# ESP32.net
KiCad netlist of a schematic drawn in Altium Designer
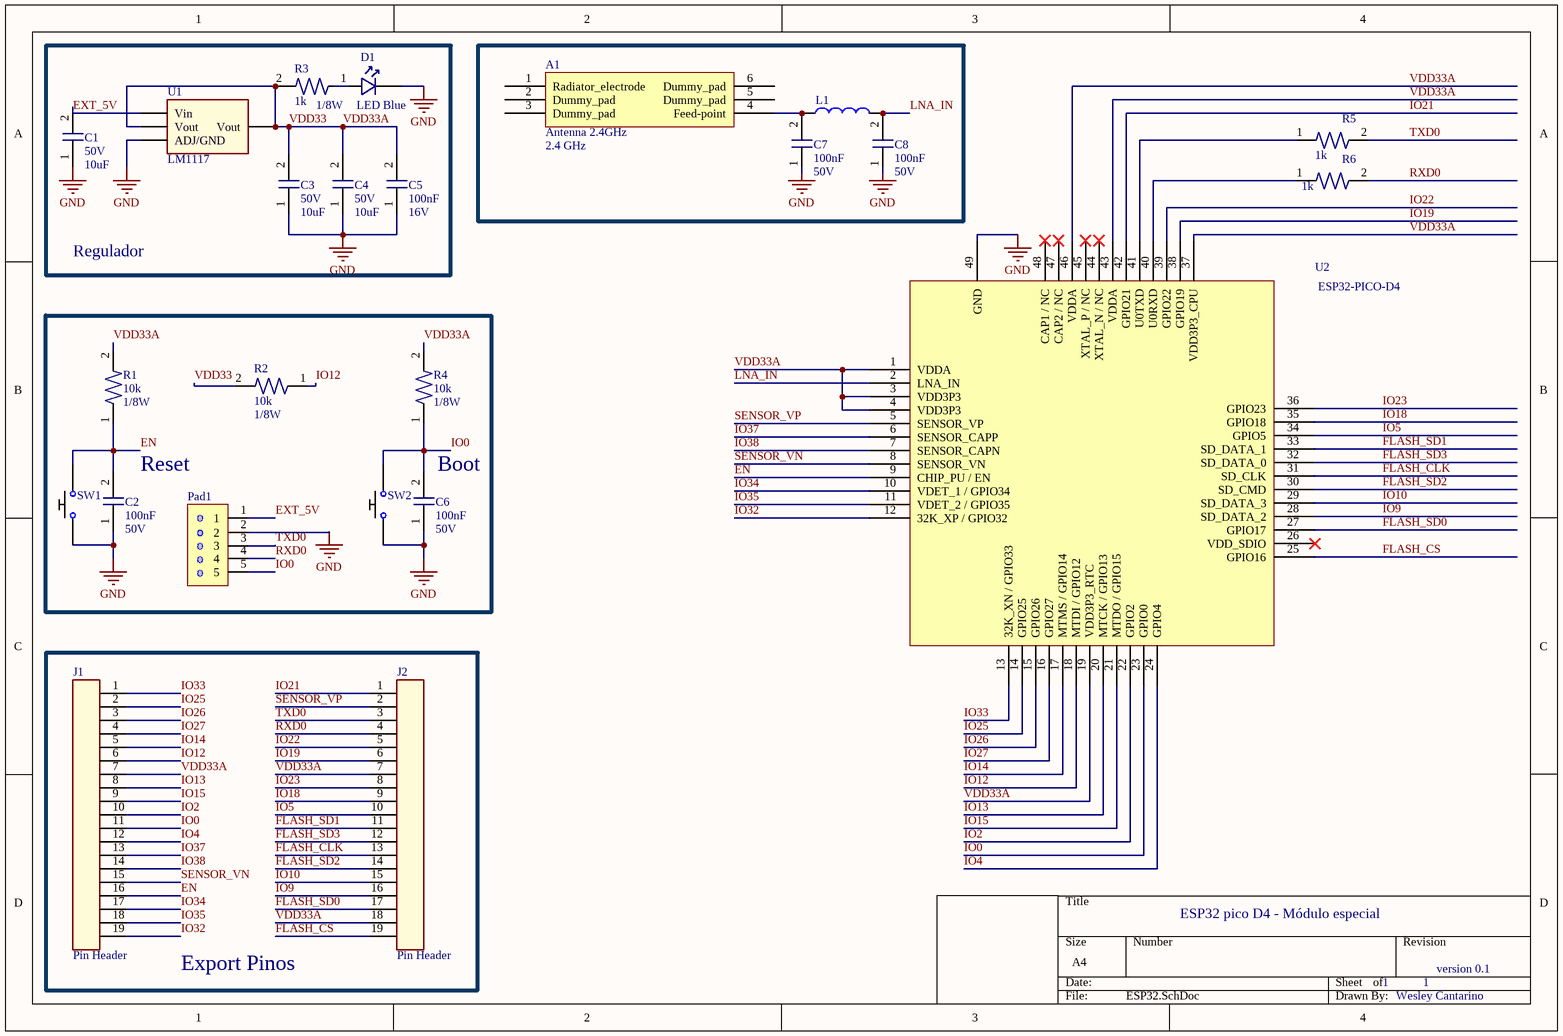
[diagram p0: ESP32.SchDoc]

(export (version "E")
  (design (tool "Eeschema 10.0.6"))
  (components
    (comp (ref "A1")
      (value "Antenna 2.4GHz")
      (footprint "PCBComponent_1")
      (description "SMD Antennas RoHS")
      (fields
        (field (name "MANUFACTURER") "TDK")
        (field (name "MFR.PART #") "ANT016008LCS2442MA2")
        (field (name "FREQUENCY RANGE") "2.4 GHz")
      )
      (libsource (lib "Antenna SMD") (part "Antenna 2.4GHz"))
    )
    (comp (ref "C1")
      (value "CAP 10uF/50V")
      (footprint "CAP 100nF/50V")
      (description "10uF ±1% 50V Ceramic Capacitor C0G, NP0 0805 (2012 Metric)")
      (fields (field (name "VOLTAGE") "50V") (field (name "CAPACITANCE") "10uF"))
      (libsource (lib "Ceramic Capacitors 0805 50V") (part "CAP  10uF/50V"))
    )
    (comp (ref "C2")
      (value "CAP 100nF/50V")
      (footprint "CAP 10uF/6.3V")
      (description "0.1µF ±10% 50V Ceramic Capacitor X5R 0402 (1005 Metric)")
      (fields (field (name "CAPACITANCE") "100nF") (field (name "VOLTAGE") "50V"))
      (libsource (lib "Capacitores SMD ceramicos") (part "CAP 100nF/50V"))
    )
    (comp (ref "C3")
      (value "CAP 10uF/50V")
      (footprint "CAP 22uF/6.3V")
      (description "10uF ±1% 50V Ceramic Capacitor C0G, NP0 0805 (2012 Metric)")
      (fields (field (name "VOLTAGE") "50V") (field (name "CAPACITANCE") "10uF"))
      (libsource (lib "Ceramic Capacitors 0805 50V") (part "CAP  10uF/50V"))
    )
    (comp (ref "C4")
      (value "CAP 10uF/50V")
      (footprint "RES SMD 62k OHM 1% 1/16W 0402")
      (description "10uF ±1% 50V Ceramic Capacitor C0G, NP0 0805 (2012 Metric)")
      (fields (field (name "VOLTAGE") "50V") (field (name "CAPACITANCE") "10uF"))
      (libsource (lib "Ceramic Capacitors 0805 50V") (part "CAP  10uF/50V"))
    )
    (comp (ref "C5")
      (value "CAP 100nF/16V")
      (footprint "RES SMD 200k OHM 1% 1/16W 0402")
      (description "0.1µF ±20% 16V Ceramic Capacitor Y5V (F) 0805 (2012 Metric)")
      (fields (field (name "CAPACITANCE") "100nF") (field (name "VOLTAGE") "16V"))
      (libsource (lib "Ceramic Capacitors 0805 16V") (part "CAP 100nF/16V"))
    )
    (comp (ref "C6")
      (value "CAP 100nF/50V")
      (footprint "CAP 22uF/6.3V")
      (description "0.1µF ±10% 50V Ceramic Capacitor X5R 0402 (1005 Metric)")
      (fields (field (name "CAPACITANCE") "100nF") (field (name "VOLTAGE") "50V"))
      (libsource (lib "Capacitores SMD ceramicos") (part "CAP 100nF/50V"))
    )
    (comp (ref "C7")
      (value "CAP 100nF/50V")
      (footprint "CAP 10uF/6.3V")
      (description "0.1µF ±10% 50V Ceramic Capacitor X5R 0402 (1005 Metric)")
      (fields (field (name "CAPACITANCE") "100nF") (field (name "VOLTAGE") "50V"))
      (libsource (lib "Ceramic Capacitors 0402 50V") (part "CAP 100nF/50V"))
    )
    (comp (ref "C8")
      (value "CAP 100nF/50V")
      (footprint "CAP 10uF/6.3V")
      (description "0.1µF ±10% 50V Ceramic Capacitor X5R 0402 (1005 Metric)")
      (fields (field (name "CAPACITANCE") "100nF") (field (name "VOLTAGE") "50V"))
      (libsource (lib "Ceramic Capacitors 0402 50V") (part "CAP 100nF/50V"))
    )
    (comp (ref "D1")
      (value "LED Blue")
      (footprint "Model Name")
      (description "Blue 470nm LED Indication - Discrete 3.3V 0805 (2012 Metric)")
      (libsource (lib "LEDs") (part "LED Blue"))
    )
    (comp (ref "J1")
      (value "Pin Header")
      (footprint "Pin Header 19 Ways")
      (description "Connector Header PTH 0.100\" (2.54mm)")
      (libsource (lib "") (part "Pin Header 19 ways_1"))
    )
    (comp (ref "J2")
      (value "Pin Header")
      (footprint "Pin Header 19 Ways")
      (description "Connector Header PTH 0.100\" (2.54mm)")
      (libsource (lib "Connectors") (part "Pin Header 19 ways"))
    )
    (comp (ref "L1")
      (value "LBEAD")
      (footprint "CAP 10uF/6.3V")
      (description "Inductor LBEAD")
      (libsource (lib "i9Library_Altium") (part "IND_LBEAD_SMD_1806"))
    )
    (comp (ref "Pad1")
      (value "CN_KK_5")
      (footprint "CN_KK_5_5045-5")
      (description "KK_5")
      (libsource (lib "i9Library_Altium") (part "CN_KK_5"))
    )
    (comp (ref "R1")
      (value "RES 0603")
      (footprint "RES SMD 0 OHM 1/16W 0402")
      (fields (field (name "RESISTENCE") "10k") (field (name "POWER") "1/8W"))
      (libsource (lib "Resistors 0603") (part "RES 10k 1% 1/8W"))
    )
    (comp (ref "R2")
      (value "RES 0603")
      (footprint "RES SMD 0 OHM 1/16W 0402")
      (fields (field (name "RESISTENCE") "10k") (field (name "POWER") "1/8W"))
      (libsource (lib "Resistors 0603") (part "RES 10k 1% 1/8W"))
    )
    (comp (ref "R3")
      (value "RES 0603")
      (footprint "RES SMD 430 OHM 1% 1/16W 0402")
      (fields (field (name "RESISTENCE") "1k") (field (name "POWER") "1/8W"))
      (libsource (lib "Resistors 0603") (part "RES 10k 1% 1/8W"))
    )
    (comp (ref "R4")
      (value "RES 0603")
      (footprint "RES SMD 0 OHM 1/16W 0402")
      (fields (field (name "RESISTENCE") "10k") (field (name "POWER") "1/8W"))
      (libsource (lib "Resistors 0603") (part "RES 10k 1% 1/8W"))
    )
    (comp (ref "R5")
      (value "RES 0603")
      (footprint "RES SMD 0 OHM 1/16W 0402")
      (fields (field (name "RESISTENCE") "1k") (field (name "POWER") "1/8W"))
      (libsource (lib "Resistors 0603") (part "RES 10k 1% 1/8W"))
    )
    (comp (ref "R6")
      (value "RES 0603")
      (footprint "RES SMD 0 OHM 1/16W 0402")
      (fields (field (name "RESISTENCE") "1k") (field (name "POWER") "1/8W"))
      (libsource (lib "Resistors 0603") (part "RES 10k 1% 1/8W"))
    )
    (comp (ref "SW1")
      (value "Tactile Switch SPST 5.10X0.40 mm")
      (footprint "PCBComponent_1")
      (description "TACTILE SWITCHES SPST 5.10MM X 5.10MM 0.40MM 50MA @ 12VDC SMD ROHS")
      (fields (field (name "MANUFACTURER") "XKB Enterprise") (field (name "MFR.PART #") "TS-1187A-B-A-B"))
      (libsource (lib "Tactile Switches SMD") (part "Tactile Switch SPST 5.10X0.40 mm"))
    )
    (comp (ref "SW2")
      (value "Tactile Switch SPST 5.10X0.40 mm")
      (footprint "PCBComponent_1")
      (description "TACTILE SWITCHES SPST 5.10MM X 5.10MM 0.40MM 50MA @ 12VDC SMD ROHS")
      (fields (field (name "MANUFACTURER") "XKB Enterprise") (field (name "MFR.PART #") "TS-1187A-B-A-B"))
      (libsource (lib "Tactile Switches SMD") (part "Tactile Switch SPST 5.10X0.40 mm"))
    )
    (comp (ref "U1")
      (value "LM1117")
      (footprint "LM1117")
      (description "Linear Voltage Regulator IC Positive Fixed 1 Output 3.3V 1A SOT-223")
      (libsource (lib "ICs - Voltage Regulators") (part "LM1117"))
    )
    (comp (ref "U2")
      (value "ESP32-PICO-D4")
      (footprint "*PQFN50P700X700X104-49N")
      (description "RF TRANSCEIVER ICS QFN-48_7X7X05P ROHS")
      (fields (field (name "MANUFACTURER") "Espressif Systems") (field (name "LCSC PART #") "C193707"))
      (libsource (lib "ESP32") (part "ESP32-PICO-D4"))
    )
  )
  (nets
    (net (code "1") (name "/EN") (class "Default")
      (node (ref "C2") (pin "2") (pinfunction "2_2") (pintype "passive"))
      (node (ref "J1") (pin "16") (pinfunction "16_16") (pintype "passive"))
      (node (ref "R1") (pin "1") (pinfunction "1_1") (pintype "passive"))
      (node (ref "SW1") (pin "2") (pinfunction "B_2") (pintype "passive"))
      (node (ref "U2") (pin "9") (pinfunction "CHIP_PU_/_EN_9") (pintype "passive"))
    )
    (net (code "2") (name "/EXT_5V") (class "Default")
      (node (ref "C1") (pin "2") (pinfunction "2_2") (pintype "passive"))
      (node (ref "Pad1") (pin "1") (pinfunction "1_1") (pintype "passive"))
      (node (ref "U1") (pin "3") (pinfunction "Vin_3") (pintype "power_in"))
    )
    (net (code "3") (name "/FLASH_CLK") (class "Default")
      (node (ref "J2") (pin "13") (pinfunction "13_13") (pintype "passive"))
      (node (ref "U2") (pin "31") (pinfunction "SD_CLK_31") (pintype "passive"))
    )
    (net (code "4") (name "/FLASH_CS") (class "Default")
      (node (ref "J2") (pin "19") (pinfunction "19_19") (pintype "passive"))
      (node (ref "U2") (pin "25") (pinfunction "GPIO16_25") (pintype "passive"))
    )
    (net (code "5") (name "/FLASH_SD0") (class "Default")
      (node (ref "J2") (pin "17") (pinfunction "17_17") (pintype "passive"))
      (node (ref "U2") (pin "27") (pinfunction "GPIO17_27") (pintype "passive"))
    )
    (net (code "6") (name "/FLASH_SD1") (class "Default")
      (node (ref "J2") (pin "11") (pinfunction "11_11") (pintype "passive"))
      (node (ref "U2") (pin "33") (pinfunction "SD_DATA_1_33") (pintype "passive"))
    )
    (net (code "7") (name "/FLASH_SD2") (class "Default")
      (node (ref "J2") (pin "14") (pinfunction "14_14") (pintype "passive"))
      (node (ref "U2") (pin "30") (pinfunction "SD_CMD_30") (pintype "passive"))
    )
    (net (code "8") (name "/FLASH_SD3") (class "Default")
      (node (ref "J2") (pin "12") (pinfunction "12_12") (pintype "passive"))
      (node (ref "U2") (pin "32") (pinfunction "SD_DATA_0_32") (pintype "passive"))
    )
    (net (code "9") (name "/IO0") (class "Default")
      (node (ref "C6") (pin "2") (pinfunction "2_2") (pintype "passive"))
      (node (ref "J1") (pin "11") (pinfunction "11_11") (pintype "passive"))
      (node (ref "Pad1") (pin "5") (pinfunction "5_5") (pintype "passive"))
      (node (ref "R4") (pin "1") (pinfunction "1_1") (pintype "passive"))
      (node (ref "SW2") (pin "2") (pinfunction "B_2") (pintype "passive"))
      (node (ref "U2") (pin "23") (pinfunction "GPIO0_23") (pintype "passive"))
    )
    (net (code "10") (name "/IO2") (class "Default")
      (node (ref "J1") (pin "10") (pinfunction "10_10") (pintype "passive"))
      (node (ref "U2") (pin "22") (pinfunction "GPIO2_22") (pintype "passive"))
    )
    (net (code "11") (name "/IO4") (class "Default")
      (node (ref "J1") (pin "12") (pinfunction "12_12") (pintype "passive"))
      (node (ref "U2") (pin "24") (pinfunction "GPIO4_24") (pintype "passive"))
    )
    (net (code "12") (name "/IO5") (class "Default")
      (node (ref "J2") (pin "10") (pinfunction "10_10") (pintype "passive"))
      (node (ref "U2") (pin "34") (pinfunction "GPIO5_34") (pintype "passive"))
    )
    (net (code "13") (name "/IO9") (class "Default")
      (node (ref "J2") (pin "16") (pinfunction "16_16") (pintype "passive"))
      (node (ref "U2") (pin "28") (pinfunction "SD_DATA_2_28") (pintype "passive"))
    )
    (net (code "14") (name "/IO10") (class "Default")
      (node (ref "J2") (pin "15") (pinfunction "15_15") (pintype "passive"))
      (node (ref "U2") (pin "29") (pinfunction "SD_DATA_3_29") (pintype "passive"))
    )
    (net (code "15") (name "/IO12") (class "Default")
      (node (ref "J1") (pin "6") (pinfunction "6_6") (pintype "passive"))
      (node (ref "R2") (pin "1") (pinfunction "1_1") (pintype "passive"))
      (node (ref "U2") (pin "18") (pinfunction "MTDI_/_GPIO12_18") (pintype "passive"))
    )
    (net (code "16") (name "/IO13") (class "Default")
      (node (ref "J1") (pin "8") (pinfunction "8_8") (pintype "passive"))
      (node (ref "U2") (pin "20") (pinfunction "MTCK_/_GPIO13_20") (pintype "passive"))
    )
    (net (code "17") (name "/IO14") (class "Default")
      (node (ref "J1") (pin "5") (pinfunction "5_5") (pintype "passive"))
      (node (ref "U2") (pin "17") (pinfunction "MTMS_/_GPIO14_17") (pintype "passive"))
    )
    (net (code "18") (name "/IO15") (class "Default")
      (node (ref "J1") (pin "9") (pinfunction "9_9") (pintype "passive"))
      (node (ref "U2") (pin "21") (pinfunction "MTDO_/_GPIO15_21") (pintype "passive"))
    )
    (net (code "19") (name "/IO18") (class "Default")
      (node (ref "J2") (pin "9") (pinfunction "9_9") (pintype "passive"))
      (node (ref "U2") (pin "35") (pinfunction "GPIO18_35") (pintype "passive"))
    )
    (net (code "20") (name "/IO19") (class "Default")
      (node (ref "J2") (pin "6") (pinfunction "6_6") (pintype "passive"))
      (node (ref "U2") (pin "38") (pinfunction "GPIO19_38") (pintype "passive"))
    )
    (net (code "21") (name "/IO21") (class "Default")
      (node (ref "J2") (pin "1") (pinfunction "1_1") (pintype "passive"))
      (node (ref "U2") (pin "42") (pinfunction "GPIO21_42") (pintype "passive"))
    )
    (net (code "22") (name "/IO22") (class "Default")
      (node (ref "J2") (pin "5") (pinfunction "5_5") (pintype "passive"))
      (node (ref "U2") (pin "39") (pinfunction "GPIO22_39") (pintype "passive"))
    )
    (net (code "23") (name "/IO23") (class "Default")
      (node (ref "J2") (pin "8") (pinfunction "8_8") (pintype "passive"))
      (node (ref "U2") (pin "36") (pinfunction "GPIO23_36") (pintype "passive"))
    )
    (net (code "24") (name "/IO25") (class "Default")
      (node (ref "J1") (pin "2") (pinfunction "2_2") (pintype "passive"))
      (node (ref "U2") (pin "14") (pinfunction "GPIO25_14") (pintype "passive"))
    )
    (net (code "25") (name "/IO26") (class "Default")
      (node (ref "J1") (pin "3") (pinfunction "3_3") (pintype "passive"))
      (node (ref "U2") (pin "15") (pinfunction "GPIO26_15") (pintype "passive"))
    )
    (net (code "26") (name "/IO27") (class "Default")
      (node (ref "J1") (pin "4") (pinfunction "4_4") (pintype "passive"))
      (node (ref "U2") (pin "16") (pinfunction "GPIO27_16") (pintype "passive"))
    )
    (net (code "27") (name "/IO32") (class "Default")
      (node (ref "J1") (pin "19") (pinfunction "19_19") (pintype "passive"))
      (node (ref "U2") (pin "12") (pinfunction "32K_XP_/_GPIO32_12") (pintype "passive"))
    )
    (net (code "28") (name "/IO33") (class "Default")
      (node (ref "J1") (pin "1") (pinfunction "1_1") (pintype "passive"))
      (node (ref "U2") (pin "13") (pinfunction "32K_XN_/_GPIO33_13") (pintype "passive"))
    )
    (net (code "29") (name "/IO34") (class "Default")
      (node (ref "J1") (pin "17") (pinfunction "17_17") (pintype "passive"))
      (node (ref "U2") (pin "10") (pinfunction "VDET_1_/_GPIO34_10") (pintype "passive"))
    )
    (net (code "30") (name "/IO35") (class "Default")
      (node (ref "J1") (pin "18") (pinfunction "18_18") (pintype "passive"))
      (node (ref "U2") (pin "11") (pinfunction "VDET_2_/_GPIO35_11") (pintype "passive"))
    )
    (net (code "31") (name "/IO37") (class "Default")
      (node (ref "J1") (pin "13") (pinfunction "13_13") (pintype "passive"))
      (node (ref "U2") (pin "6") (pinfunction "SENSOR_CAPP_6") (pintype "passive"))
    )
    (net (code "32") (name "/IO38") (class "Default")
      (node (ref "J1") (pin "14") (pinfunction "14_14") (pintype "passive"))
      (node (ref "U2") (pin "7") (pinfunction "SENSOR_CAPN_7") (pintype "passive"))
    )
    (net (code "33") (name "/LNA_IN") (class "Default")
      (node (ref "C8") (pin "2") (pinfunction "2_2") (pintype "passive"))
      (node (ref "L1") (pin "2") (pintype "passive"))
      (node (ref "U2") (pin "2") (pinfunction "LNA_IN_2") (pintype "passive"))
    )
    (net (code "34") (name "/RXD0") (class "Default")
      (node (ref "J2") (pin "4") (pinfunction "4_4") (pintype "passive"))
      (node (ref "Pad1") (pin "4") (pinfunction "4_4") (pintype "passive"))
      (node (ref "R6") (pin "2") (pinfunction "2_2") (pintype "passive"))
    )
    (net (code "35") (name "/SENSOR_VN") (class "Default")
      (node (ref "J1") (pin "15") (pinfunction "15_15") (pintype "passive"))
      (node (ref "U2") (pin "8") (pinfunction "SENSOR_VN_8") (pintype "passive"))
    )
    (net (code "36") (name "/SENSOR_VP") (class "Default")
      (node (ref "J2") (pin "2") (pinfunction "2_2") (pintype "passive"))
      (node (ref "U2") (pin "5") (pinfunction "SENSOR_VP_5") (pintype "passive"))
    )
    (net (code "37") (name "/TXD0") (class "Default")
      (node (ref "J2") (pin "3") (pinfunction "3_3") (pintype "passive"))
      (node (ref "Pad1") (pin "3") (pinfunction "3_3") (pintype "passive"))
      (node (ref "R5") (pin "2") (pinfunction "2_2") (pintype "passive"))
    )
    (net (code "38") (name "/VDD33") (class "Default")
      (node (ref "C3") (pin "2") (pinfunction "2_2") (pintype "passive"))
      (node (ref "C4") (pin "2") (pinfunction "2_2") (pintype "passive"))
      (node (ref "C5") (pin "2") (pinfunction "2_2") (pintype "passive"))
      (node (ref "J1") (pin "7") (pinfunction "7_7") (pintype "passive"))
      (node (ref "J2") (pin "18") (pinfunction "18_18") (pintype "passive"))
      (node (ref "J2") (pin "7") (pinfunction "7_7") (pintype "passive"))
      (node (ref "R1") (pin "2") (pinfunction "2_2") (pintype "passive"))
      (node (ref "R2") (pin "2") (pinfunction "2_2") (pintype "passive"))
      (node (ref "R3") (pin "2") (pinfunction "2_2") (pintype "passive"))
      (node (ref "R4") (pin "2") (pinfunction "2_2") (pintype "passive"))
      (node (ref "U1") (pin "2") (pinfunction "Vout_2") (pintype "power_in"))
      (node (ref "U1") (pin "4") (pinfunction "Vout_4") (pintype "power_in"))
      (node (ref "U2") (pin "1") (pinfunction "VDDA_1") (pintype "passive"))
      (node (ref "U2") (pin "19") (pinfunction "VDD3P3_RTC_19") (pintype "passive"))
      (node (ref "U2") (pin "3") (pinfunction "VDD3P3_3") (pintype "passive"))
      (node (ref "U2") (pin "37") (pinfunction "VDD3P3_CPU_37") (pintype "passive"))
      (node (ref "U2") (pin "4") (pinfunction "VDD3P3_4") (pintype "passive"))
      (node (ref "U2") (pin "43") (pinfunction "VDDA_43") (pintype "passive"))
      (node (ref "U2") (pin "46") (pinfunction "VDDA_46") (pintype "passive"))
    )
    (net (code "39") (name "GND") (class "Default")
      (node (ref "C1") (pin "1") (pinfunction "1_1") (pintype "passive"))
      (node (ref "C2") (pin "1") (pinfunction "1_1") (pintype "passive"))
      (node (ref "C3") (pin "1") (pinfunction "1_1") (pintype "passive"))
      (node (ref "C4") (pin "1") (pinfunction "1_1") (pintype "passive"))
      (node (ref "C5") (pin "1") (pinfunction "1_1") (pintype "passive"))
      (node (ref "C6") (pin "1") (pinfunction "1_1") (pintype "passive"))
      (node (ref "C7") (pin "1") (pinfunction "1_1") (pintype "passive"))
      (node (ref "C8") (pin "1") (pinfunction "1_1") (pintype "passive"))
      (node (ref "D1") (pin "K") (pinfunction "K_K") (pintype "passive"))
      (node (ref "Pad1") (pin "2") (pinfunction "2_2") (pintype "passive"))
      (node (ref "SW1") (pin "1") (pinfunction "A_1") (pintype "passive"))
      (node (ref "SW2") (pin "1") (pinfunction "A_1") (pintype "passive"))
      (node (ref "U1") (pin "1") (pinfunction "ADJ/GND_1") (pintype "power_in"))
      (node (ref "U2") (pin "49") (pinfunction "GND_49") (pintype "passive"))
    )
    (net (code "40") (name "Net-(A1-Feed-point)") (class "Default")
      (node (ref "A1") (pin "4") (pinfunction "Feed-point_4") (pintype "passive"))
      (node (ref "C7") (pin "2") (pinfunction "2_2") (pintype "passive"))
      (node (ref "L1") (pin "1") (pintype "passive"))
    )
    (net (code "41") (name "Net-(D1-PadA)") (class "Default")
      (node (ref "D1") (pin "A") (pinfunction "A_A") (pintype "passive"))
      (node (ref "R3") (pin "1") (pinfunction "1_1") (pintype "passive"))
    )
    (net (code "42") (name "Net-(U2-U0RXD)") (class "Default")
      (node (ref "R6") (pin "1") (pinfunction "1_1") (pintype "passive"))
      (node (ref "U2") (pin "40") (pinfunction "U0RXD_40") (pintype "passive"))
    )
    (net (code "43") (name "Net-(U2-U0TXD)") (class "Default")
      (node (ref "R5") (pin "1") (pinfunction "1_1") (pintype "passive"))
      (node (ref "U2") (pin "41") (pinfunction "U0TXD_41") (pintype "passive"))
    )
    (net (code "44") (name "unconnected-(A1-Dummy_pad-Pad2)") (class "Default")
      (node (ref "A1") (pin "2") (pinfunction "Dummy_pad_2") (pintype "passive"))
    )
    (net (code "45") (name "unconnected-(A1-Dummy_pad-Pad3)") (class "Default")
      (node (ref "A1") (pin "3") (pinfunction "Dummy_pad_3") (pintype "passive"))
    )
    (net (code "46") (name "unconnected-(A1-Dummy_pad-Pad5)") (class "Default")
      (node (ref "A1") (pin "5") (pinfunction "Dummy_pad_5") (pintype "passive"))
    )
    (net (code "47") (name "unconnected-(A1-Dummy_pad-Pad6)") (class "Default")
      (node (ref "A1") (pin "6") (pinfunction "Dummy_pad_6") (pintype "passive"))
    )
    (net (code "48") (name "unconnected-(A1-Radiator_electrode-Pad1)") (class "Default")
      (node (ref "A1") (pin "1") (pinfunction "Radiator_electrode_1") (pintype "passive"))
    )
    (net (code "49") (name "unconnected-(U2-CAP1_{slash}_NC-Pad48)") (class "Default")
      (node (ref "U2") (pin "48") (pinfunction "CAP1_/_NC_48") (pintype "passive+no_connect"))
    )
    (net (code "50") (name "unconnected-(U2-CAP2_{slash}_NC-Pad47)") (class "Default")
      (node (ref "U2") (pin "47") (pinfunction "CAP2_/_NC_47") (pintype "passive+no_connect"))
    )
    (net (code "51") (name "unconnected-(U2-VDD_SDIO-Pad26)") (class "Default")
      (node (ref "U2") (pin "26") (pinfunction "VDD_SDIO_26") (pintype "passive+no_connect"))
    )
    (net (code "52") (name "unconnected-(U2-XTAL_N_{slash}_NC-Pad44)") (class "Default")
      (node (ref "U2") (pin "44") (pinfunction "XTAL_N_/_NC_44") (pintype "passive+no_connect"))
    )
    (net (code "53") (name "unconnected-(U2-XTAL_P_{slash}_NC-Pad45)") (class "Default")
      (node (ref "U2") (pin "45") (pinfunction "XTAL_P_/_NC_45") (pintype "passive+no_connect"))
    )
  )
)
